# LVDS_repeater.net
KiCad netlist of a schematic drawn in Altium Designer
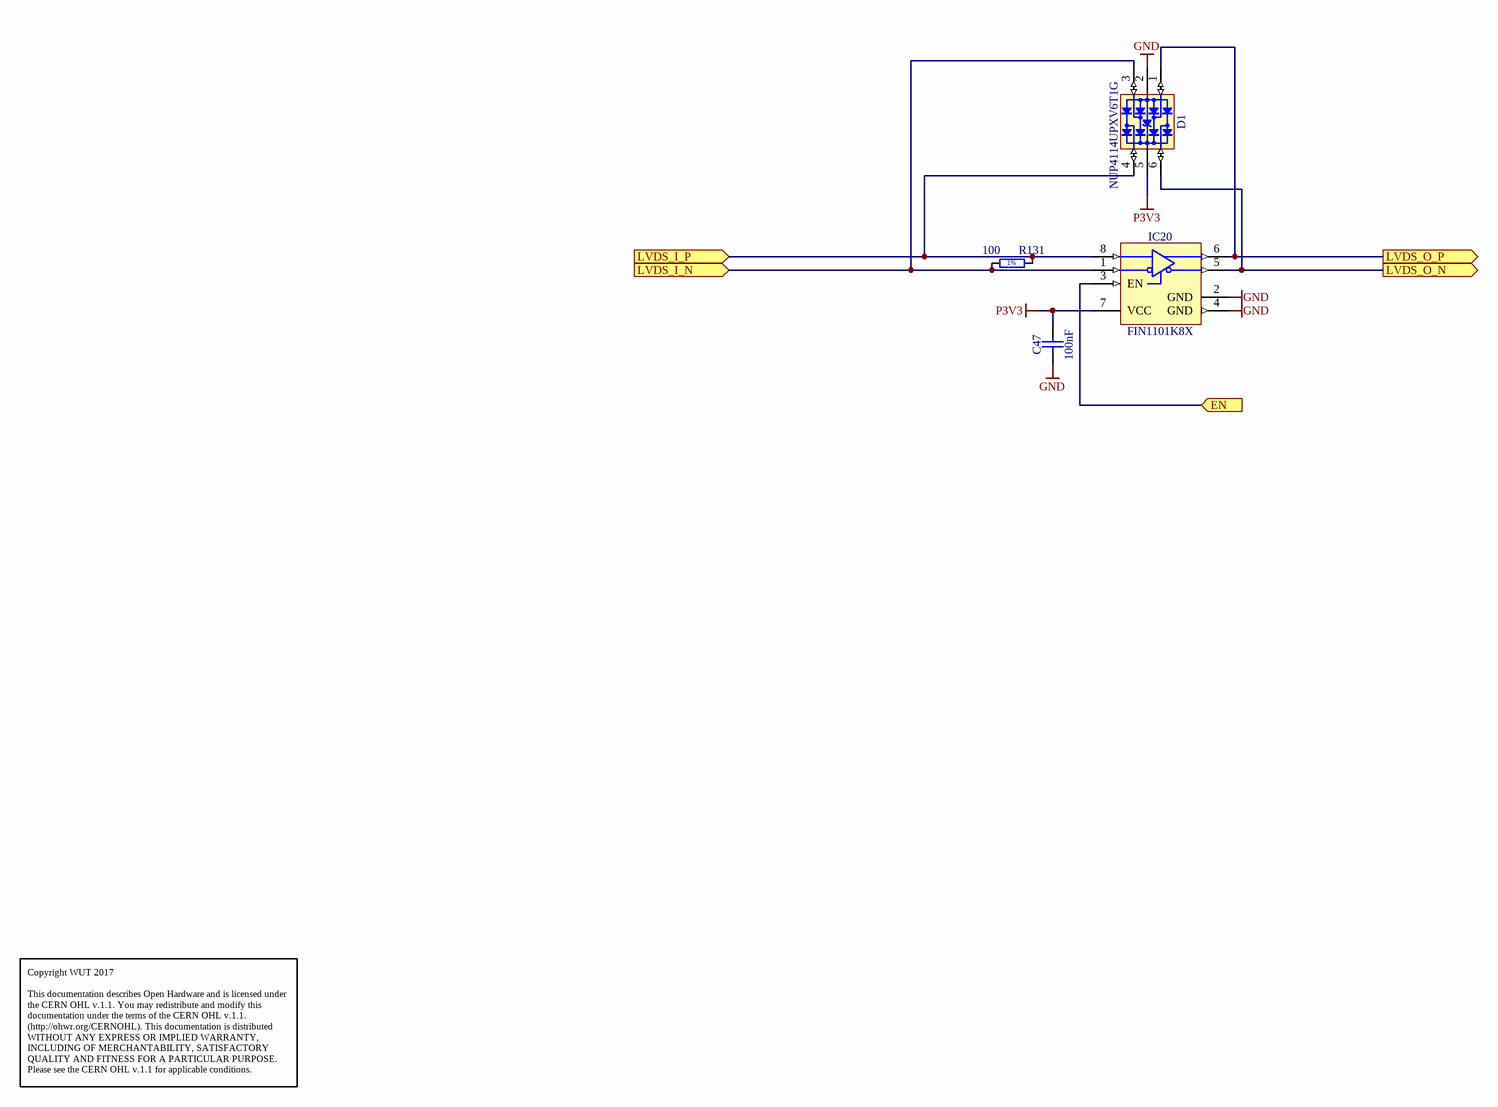
[diagram p0: LVDS_repeater.SchDoc]

(export (version "E")
  (design (tool "Eeschema 10.0.6"))
  (components
    (comp (ref "C47")
      (value "100nF")
      (footprint "CAPC1005X55N")
      (description "Non-polarised capacitor")
      (fields
        (field (name "PART NUMBER") "CC0402_100NF_16V_10%_X5R")
        (field (name "VOLTAGE") "16V")
        (field (name "AUTHOR") "CERN DEM JLC")
      )
      (libsource (lib "Capacitors") (part "Capacitor - non polarized"))
    )
    (comp (ref "D1")
      (value "NUP4114UPXV6T1G")
      (footprint "SOTFL50P160X60-6N")
      (fields
        (field (name "VOLTAGE") "5.5V")
        (field (name "MANUFACTURER") "ON SEMICONDUCTOR")
        (field (name "AUTHOR") "CERN DEM JLC")
      )
      (libsource (lib "ICs And Semiconductors") (part "NUP4114"))
    )
    (comp (ref "IC20")
      (value "FIN1101K8X")
      (footprint "SOP50P310X90-8N")
      (description "LVDS Single Port High Speed Repeater")
      (fields (field (name "MANUFACTURER") "FAIRCHILD SEMICONDUCTOR") (field (name "AUTHOR") "CERN DEM JLC"))
      (libsource (lib "ICs And Semiconductors") (part "FIN1101K8X"))
    )
    (comp (ref "R131")
      (value "100")
      (footprint "RESC1005X40N")
      (description "Resistor - 1%")
      (fields
        (field (name "PART NUMBER") "R0402_100R_1%_0.1W_100PPM")
        (field (name "POWER") "0.1W")
        (field (name "AUTHOR") "CERN DEM JLC")
      )
      (libsource (lib "Resistors") (part "Resistor - 1%"))
    )
  )
  (nets
    (net (code "1") (name "/EN") (class "Default")
      (node (ref "IC20") (pin "3") (pinfunction "EN_3") (pintype "input"))
    )
    (net (code "2") (name "/LVDS_I_N") (class "Default")
      (node (ref "D1") (pin "3") (pinfunction "I/O2_3") (pintype "bidirectional"))
      (node (ref "IC20") (pin "1") (pinfunction "RIN-_1") (pintype "input"))
      (node (ref "R131") (pin "1") (pinfunction "1_1") (pintype "passive"))
    )
    (net (code "3") (name "/LVDS_I_P") (class "Default")
      (node (ref "D1") (pin "4") (pinfunction "I/O3_4") (pintype "bidirectional"))
      (node (ref "IC20") (pin "8") (pinfunction "RIN+_8") (pintype "input"))
      (node (ref "R131") (pin "2") (pinfunction "2_2") (pintype "passive"))
    )
    (net (code "4") (name "/LVDS_O_N") (class "Default")
      (node (ref "D1") (pin "6") (pinfunction "I/O4_6") (pintype "bidirectional"))
      (node (ref "IC20") (pin "5") (pinfunction "DOUT-_5") (pintype "output"))
    )
    (net (code "5") (name "/LVDS_O_P") (class "Default")
      (node (ref "D1") (pin "1") (pinfunction "I/O1_1") (pintype "bidirectional"))
      (node (ref "IC20") (pin "6") (pinfunction "DOUT+_6") (pintype "output"))
    )
    (net (code "6") (name "GND") (class "Default")
      (node (ref "C47") (pin "1") (pinfunction "1_1") (pintype "passive"))
      (node (ref "D1") (pin "2") (pinfunction "GND_2") (pintype "power_in"))
      (node (ref "IC20") (pin "2") (pinfunction "GND_2") (pintype "power_in"))
      (node (ref "IC20") (pin "4") (pinfunction "GND_4") (pintype "output"))
    )
    (net (code "7") (name "P3V3") (class "Default")
      (node (ref "C47") (pin "2") (pinfunction "2_2") (pintype "passive"))
      (node (ref "D1") (pin "5") (pinfunction "VBUS_5") (pintype "power_in"))
      (node (ref "IC20") (pin "7") (pinfunction "VCC_7") (pintype "power_in"))
    )
  )
)
